# USB_Device.net
KiCad netlist of a schematic drawn in Altium Designer
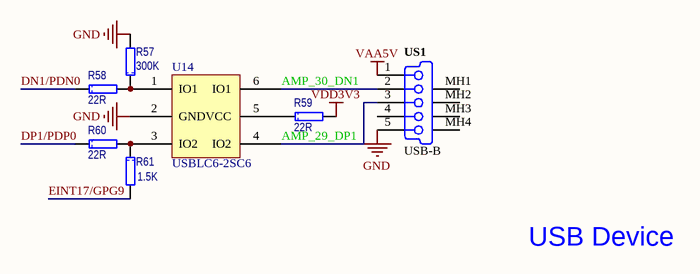
[diagram p0: USB Device.SchDoc]

(export (version "E")
  (design (tool "Eeschema 10.0.6"))
  (components
    (comp (ref "R57")
      (value "300K")
      (footprint "1608[0603]R")
      (description "RES")
      (fields (field (name "MANUFACTURER") "vishay"))
      (libsource (lib "*") (part "RES"))
    )
    (comp (ref "R58")
      (value "22R")
      (footprint "1608[0603]R")
      (description "RES")
      (fields (field (name "MANUFACTURER") "vishay"))
      (libsource (lib "*") (part "RES"))
    )
    (comp (ref "R59")
      (value "22R")
      (footprint "1608[0603]R")
      (description "RES")
      (fields (field (name "MANUFACTURER") "vishay"))
      (libsource (lib "*") (part "RES"))
    )
    (comp (ref "R60")
      (value "22R")
      (footprint "1608[0603]R")
      (description "RES")
      (fields (field (name "MANUFACTURER") "vishay"))
      (libsource (lib "*") (part "RES"))
    )
    (comp (ref "R61")
      (value "1.5K")
      (footprint "1608[0603]R")
      (description "RES")
      (fields (field (name "MANUFACTURER") "vishay"))
      (libsource (lib "*") (part "RES"))
    )
    (comp (ref "U14")
      (value "USBLC6-2SC6")
      (footprint "SOT26A-6N")
      (description "ESD")
      (libsource (lib "S3C2440V9") (part "USBLC6-2SC6"))
    )
    (comp (ref "US1")
      (value "USB-B")
      (footprint "USB/SM0.8-6H5")
      (libsource (lib "AltiumDesignLibrary") (part "0481900001"))
    )
  )
  (nets
    (net (code "1") (name "/AMP_29_DP1") (class "Default")
      (node (ref "U14") (pin "4") (pinfunction "IO2_4") (pintype "passive"))
      (node (ref "US1") (pin "3") (pinfunction "3_3") (pintype "passive"))
    )
    (net (code "2") (name "/AMP_30_DN1") (class "Default")
      (node (ref "U14") (pin "6") (pinfunction "IO1_6") (pintype "passive"))
      (node (ref "US1") (pin "2") (pinfunction "2_2") (pintype "passive"))
    )
    (net (code "3") (name "/DN1{slash}PDN0") (class "Default")
      (node (ref "R58") (pin "1") (pinfunction "1_1") (pintype "passive"))
    )
    (net (code "4") (name "/DP1{slash}PDP0") (class "Default")
      (node (ref "R60") (pin "1") (pinfunction "1_1") (pintype "passive"))
    )
    (net (code "5") (name "/EINT17{slash}GPG9") (class "Default")
      (node (ref "R61") (pin "2") (pinfunction "2_2") (pintype "passive"))
    )
    (net (code "6") (name "GND") (class "Default")
      (node (ref "R57") (pin "2") (pinfunction "2_2") (pintype "passive"))
      (node (ref "U14") (pin "2") (pinfunction "GND_2") (pintype "passive"))
      (node (ref "US1") (pin "5") (pinfunction "5_5") (pintype "passive"))
    )
    (net (code "7") (name "Net-(R57-Pad1)") (class "Default")
      (node (ref "R57") (pin "1") (pinfunction "1_1") (pintype "passive"))
      (node (ref "R58") (pin "2") (pinfunction "2_2") (pintype "passive"))
      (node (ref "U14") (pin "1") (pinfunction "IO1_1") (pintype "passive"))
    )
    (net (code "8") (name "Net-(R60-Pad2)") (class "Default")
      (node (ref "R60") (pin "2") (pinfunction "2_2") (pintype "passive"))
      (node (ref "R61") (pin "1") (pinfunction "1_1") (pintype "passive"))
      (node (ref "U14") (pin "3") (pinfunction "IO2_3") (pintype "passive"))
    )
    (net (code "9") (name "Net-(U14-VCC)") (class "Default")
      (node (ref "R59") (pin "1") (pinfunction "1_1") (pintype "passive"))
      (node (ref "U14") (pin "5") (pinfunction "VCC_5") (pintype "passive"))
    )
    (net (code "10") (name "VAA5V") (class "Default")
      (node (ref "US1") (pin "1") (pinfunction "1_1") (pintype "passive"))
    )
    (net (code "11") (name "VDD3V3") (class "Default")
      (node (ref "R59") (pin "2") (pinfunction "2_2") (pintype "passive"))
    )
    (net (code "12") (name "unconnected-(US1-Pad4)") (class "Default")
      (node (ref "US1") (pin "4") (pinfunction "4_4") (pintype "passive"))
    )
    (net (code "13") (name "unconnected-(US1-PadMH1)") (class "Default")
      (node (ref "US1") (pin "MH1") (pinfunction "MH1_MH1") (pintype "passive"))
    )
    (net (code "14") (name "unconnected-(US1-PadMH2)") (class "Default")
      (node (ref "US1") (pin "MH2") (pinfunction "MH2_MH2") (pintype "passive"))
    )
    (net (code "15") (name "unconnected-(US1-PadMH3)") (class "Default")
      (node (ref "US1") (pin "MH3") (pinfunction "MH3_MH3") (pintype "passive"))
    )
    (net (code "16") (name "unconnected-(US1-PadMH4)") (class "Default")
      (node (ref "US1") (pin "MH4") (pinfunction "MH4_MH4") (pintype "passive"))
    )
  )
)
